# diagram.net
KiCad netlist of a schematic drawn in EAGLE
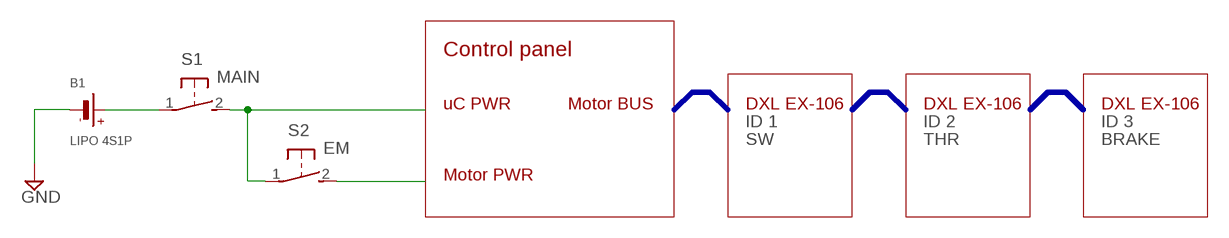
[diagram p0: schematic, sheet 1]

(export (version "E")
  (design (tool "Eeschema 10.0.6"))
  (components
    (comp (ref "B1")
      (value "LIPO 4S1P")
      (footprint "eagle-import:JSTPH2")
      (libsource (lib "eagle-import") (part "BATTERY"))
    )
    (comp (ref "S1")
      (value "MAIN")
      (footprint "eagle-import:B3F-31XX")
      (libsource (lib "eagle-import") (part "31-XX"))
    )
    (comp (ref "S2")
      (value "EM")
      (footprint "eagle-import:B3F-31XX")
      (libsource (lib "eagle-import") (part "31-XX"))
    )
  )
  (nets
    (net (code "1") (name "GND") (class "Default")
      (node (ref "B1") (pin "1") (pinfunction "-_1") (pintype "passive"))
    )
    (net (code "2") (name "Net-(B1-+)") (class "Default")
      (node (ref "B1") (pin "2") (pinfunction "+_2") (pintype "passive"))
      (node (ref "S1") (pin "1") (pinfunction "P_1") (pintype "passive"))
    )
    (net (code "3") (name "Net-(S1-S)") (class "Default")
      (node (ref "S1") (pin "2") (pinfunction "S_2") (pintype "passive"))
      (node (ref "S2") (pin "1") (pinfunction "P_1") (pintype "passive"))
    )
    (net (code "4") (name "unconnected-(S2-S-Pad2)") (class "Default")
      (node (ref "S2") (pin "2") (pinfunction "S_2") (pintype "passive"))
    )
  )
)
